# broken_harness_sheet.net
KiCad netlist of a schematic drawn in Altium Designer
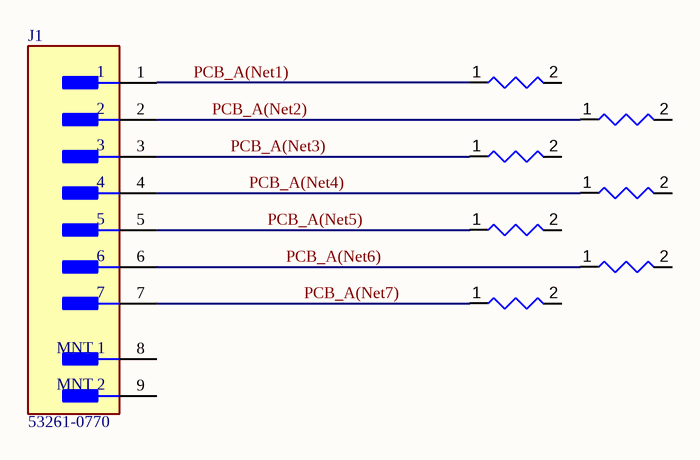
[diagram p0: broken_harness_sheet.SchDoc]

(export (version "E")
  (design (tool "Eeschema 10.0.6"))
  (components
    (comp (ref "J1")
      (value "53261-0770")
      (footprint "PCB2:FP-53261-0771-MFG")
      (fields (field (name "MANUFACTURER") "Molex") (field (name "MANUFACTURER PART NUMBER") "53261-0771"))
      (libsource (lib "Harness_Demo_PCB_A") (part "CMP-002-00075-1"))
    )
    (comp (ref "R1")
      (value "Resistor 10k +/-1% 1206 250 mW")
      (footprint "RESC3216X60X45ML15T20")
      (description "Chip Resistor, 10 KOhm, +/- 1%, 0.25 W, -55 to 155 degC, 1206 (3216 Metric)")
      (fields (field (name "TOLERANCE") "1%") (field (name "POWER") "250mW"))
      (libsource (lib "SCH") (part "RES-2"))
    )
    (comp (ref "R2")
      (value "Resistor 10k +/-1% 1206 250 mW")
      (footprint "RESC3216X60X45ML15T20")
      (description "Chip Resistor, 10 KOhm, +/- 1%, 0.25 W, -55 to 155 degC, 1206 (3216 Metric)")
      (fields (field (name "TOLERANCE") "1%") (field (name "POWER") "250mW"))
      (libsource (lib "SCH") (part "RES-2"))
    )
    (comp (ref "R3")
      (value "Resistor 10k +/-1% 1206 250 mW")
      (footprint "RESC3216X60X45ML15T20")
      (description "Chip Resistor, 10 KOhm, +/- 1%, 0.25 W, -55 to 155 degC, 1206 (3216 Metric)")
      (fields (field (name "TOLERANCE") "1%") (field (name "POWER") "250mW"))
      (libsource (lib "SCH") (part "RES-2"))
    )
    (comp (ref "R4")
      (value "Resistor 10k +/-1% 1206 250 mW")
      (footprint "RESC3216X60X45ML15T20")
      (description "Chip Resistor, 10 KOhm, +/- 1%, 0.25 W, -55 to 155 degC, 1206 (3216 Metric)")
      (fields (field (name "TOLERANCE") "1%") (field (name "POWER") "250mW"))
      (libsource (lib "SCH") (part "RES-2"))
    )
    (comp (ref "R5")
      (value "Resistor 10k +/-1% 1206 250 mW")
      (footprint "RESC3216X60X45ML15T20")
      (description "Chip Resistor, 10 KOhm, +/- 1%, 0.25 W, -55 to 155 degC, 1206 (3216 Metric)")
      (fields (field (name "TOLERANCE") "1%") (field (name "POWER") "250mW"))
      (libsource (lib "SCH") (part "RES-2"))
    )
    (comp (ref "R6")
      (value "Resistor 10k +/-5% 1206 250 mW")
      (footprint "RESC3216X60X45ML15T20")
      (description "Chip Resistor, 10 KOhm, +/- 1%, 0.25 W, -55 to 155 degC, 1206 (3216 Metric)")
      (fields (field (name "TOLERANCE") "1%") (field (name "POWER") "250mW"))
      (libsource (lib "SCH") (part "RES-2"))
    )
    (comp (ref "R7")
      (value "Resistor 10k +/-1% 1206 250 mW")
      (footprint "RESC3216X60X45ML15T20")
      (description "Chip Resistor, 10 KOhm, +/- 1%, 0.25 W, -55 to 155 degC, 1206 (3216 Metric)")
      (fields (field (name "TOLERANCE") "1%") (field (name "POWER") "250mW"))
      (libsource (lib "SCH") (part "RES-2"))
    )
  )
  (nets
    (net (code "1") (name "/PCB_A(Net1)") (class "Default")
      (node (ref "J1") (pin "1") (pinfunction "1_1") (pintype "passive"))
      (node (ref "R1") (pin "1") (pinfunction "1_1") (pintype "passive"))
    )
    (net (code "2") (name "/PCB_A(Net2)") (class "Default")
      (node (ref "J1") (pin "2") (pinfunction "2_2") (pintype "passive"))
      (node (ref "R2") (pin "1") (pinfunction "1_1") (pintype "passive"))
    )
    (net (code "3") (name "/PCB_A(Net3)") (class "Default")
      (node (ref "J1") (pin "3") (pinfunction "3_3") (pintype "passive"))
      (node (ref "R3") (pin "1") (pinfunction "1_1") (pintype "passive"))
    )
    (net (code "4") (name "/PCB_A(Net4)") (class "Default")
      (node (ref "J1") (pin "4") (pinfunction "4_4") (pintype "passive"))
      (node (ref "R4") (pin "1") (pinfunction "1_1") (pintype "passive"))
    )
    (net (code "5") (name "/PCB_A(Net5)") (class "Default")
      (node (ref "J1") (pin "5") (pinfunction "5_5") (pintype "passive"))
      (node (ref "R5") (pin "1") (pinfunction "1_1") (pintype "passive"))
    )
    (net (code "6") (name "/PCB_A(Net6)") (class "Default")
      (node (ref "J1") (pin "6") (pinfunction "6_6") (pintype "passive"))
      (node (ref "R6") (pin "1") (pinfunction "1_1") (pintype "passive"))
    )
    (net (code "7") (name "/PCB_A(Net7)") (class "Default")
      (node (ref "J1") (pin "7") (pinfunction "7_7") (pintype "passive"))
      (node (ref "R7") (pin "1") (pinfunction "1_1") (pintype "passive"))
    )
    (net (code "8") (name "unconnected-(J1-MNT_1-Pad8)") (class "Default")
      (node (ref "J1") (pin "8") (pinfunction "MNT_1_8") (pintype "passive"))
    )
    (net (code "9") (name "unconnected-(J1-MNT_2-Pad9)") (class "Default")
      (node (ref "J1") (pin "9") (pinfunction "MNT_2_9") (pintype "passive"))
    )
    (net (code "10") (name "unconnected-(R1-Pad2)") (class "Default")
      (node (ref "R1") (pin "2") (pinfunction "2_2") (pintype "passive"))
    )
    (net (code "11") (name "unconnected-(R2-Pad2)") (class "Default")
      (node (ref "R2") (pin "2") (pinfunction "2_2") (pintype "passive"))
    )
    (net (code "12") (name "unconnected-(R3-Pad2)") (class "Default")
      (node (ref "R3") (pin "2") (pinfunction "2_2") (pintype "passive"))
    )
    (net (code "13") (name "unconnected-(R4-Pad2)") (class "Default")
      (node (ref "R4") (pin "2") (pinfunction "2_2") (pintype "passive"))
    )
    (net (code "14") (name "unconnected-(R5-Pad2)") (class "Default")
      (node (ref "R5") (pin "2") (pinfunction "2_2") (pintype "passive"))
    )
    (net (code "15") (name "unconnected-(R6-Pad2)") (class "Default")
      (node (ref "R6") (pin "2") (pinfunction "2_2") (pintype "passive"))
    )
    (net (code "16") (name "unconnected-(R7-Pad2)") (class "Default")
      (node (ref "R7") (pin "2") (pinfunction "2_2") (pintype "passive"))
    )
  )
)
